# B130B.net
KiCad netlist of a schematic drawn in EAGLE
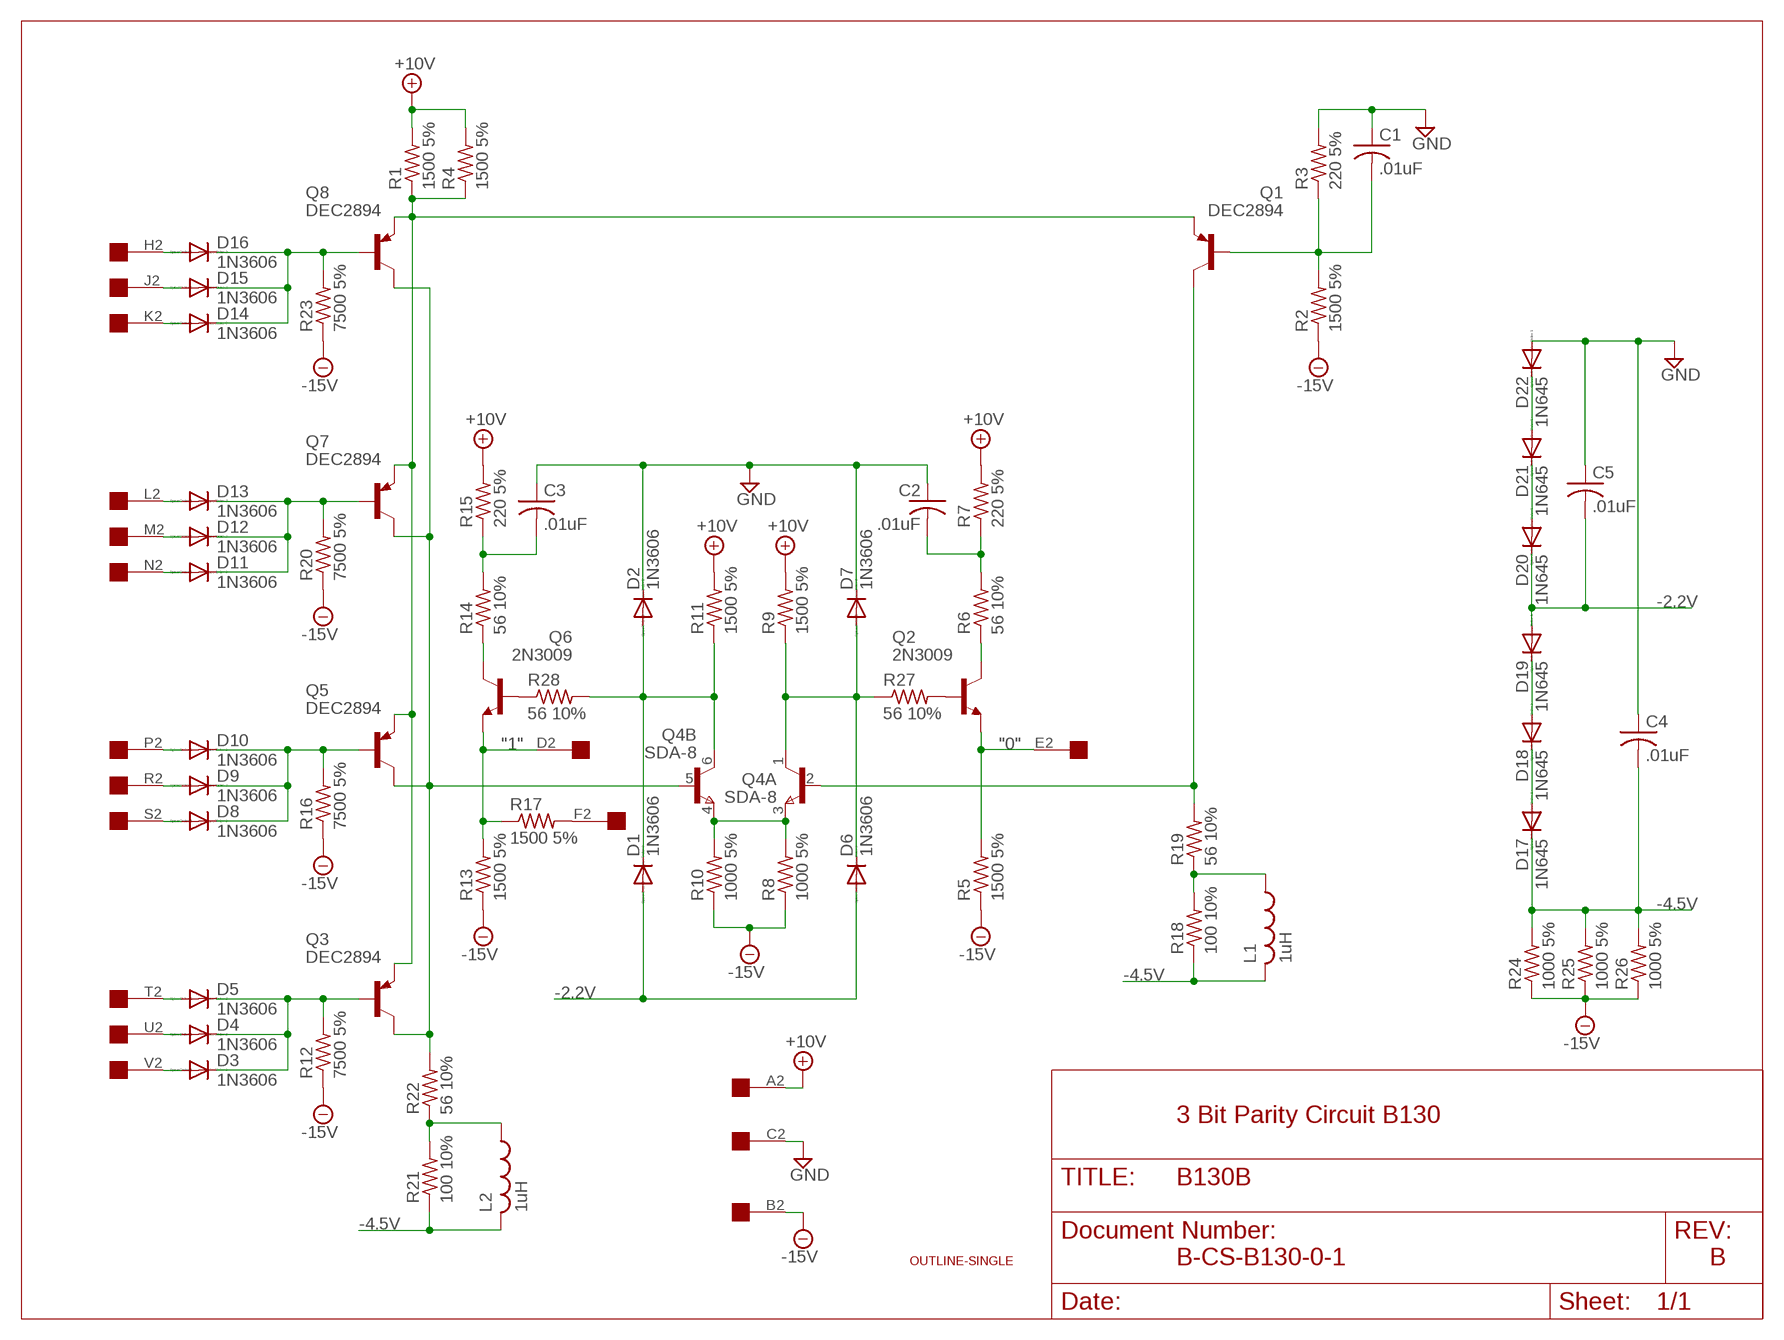
[diagram p0: schematic, sheet 1]

(export (version "E")
  (design (tool "Eeschema 10.0.6"))
  (components
    (comp (ref "C1")
      (value ".01uF")
      (footprint "eagle-import:C050-025X075")
      (libsource (lib "eagle-import") (part "C-US050-025X075"))
    )
    (comp (ref "C2")
      (value ".01uF")
      (footprint "eagle-import:C050-025X075")
      (libsource (lib "eagle-import") (part "C-US050-025X075"))
    )
    (comp (ref "C3")
      (value ".01uF")
      (footprint "eagle-import:C050-025X075")
      (libsource (lib "eagle-import") (part "C-US050-025X075"))
    )
    (comp (ref "C4")
      (value ".01uF")
      (footprint "eagle-import:C050-025X075")
      (libsource (lib "eagle-import") (part "C-US050-025X075"))
    )
    (comp (ref "C5")
      (value ".01uF")
      (footprint "eagle-import:C050-025X075")
      (libsource (lib "eagle-import") (part "C-US050-025X075"))
    )
    (comp (ref "D1")
      (value "1N3606")
      (footprint "eagle-import:DO35-10")
      (libsource (lib "eagle-import") (part "1N4148DO35-10"))
    )
    (comp (ref "D2")
      (value "1N3606")
      (footprint "eagle-import:DO35-10")
      (libsource (lib "eagle-import") (part "1N4148DO35-10"))
    )
    (comp (ref "D3")
      (value "1N3606")
      (footprint "eagle-import:DO35-10")
      (libsource (lib "eagle-import") (part "1N4148DO35-10"))
    )
    (comp (ref "D4")
      (value "1N3606")
      (footprint "eagle-import:DO35-10")
      (libsource (lib "eagle-import") (part "1N4148DO35-10"))
    )
    (comp (ref "D5")
      (value "1N3606")
      (footprint "eagle-import:DO35-10")
      (libsource (lib "eagle-import") (part "1N4148DO35-10"))
    )
    (comp (ref "D6")
      (value "1N3606")
      (footprint "eagle-import:DO35-10")
      (libsource (lib "eagle-import") (part "1N4148DO35-10"))
    )
    (comp (ref "D7")
      (value "1N3606")
      (footprint "eagle-import:DO35-10")
      (libsource (lib "eagle-import") (part "1N4148DO35-10"))
    )
    (comp (ref "D8")
      (value "1N3606")
      (footprint "eagle-import:DO35-10")
      (libsource (lib "eagle-import") (part "1N4148DO35-10"))
    )
    (comp (ref "D9")
      (value "1N3606")
      (footprint "eagle-import:DO35-10")
      (libsource (lib "eagle-import") (part "1N4148DO35-10"))
    )
    (comp (ref "D10")
      (value "1N3606")
      (footprint "eagle-import:DO35-10")
      (libsource (lib "eagle-import") (part "1N4148DO35-10"))
    )
    (comp (ref "D11")
      (value "1N3606")
      (footprint "eagle-import:DO35-10")
      (libsource (lib "eagle-import") (part "1N4148DO35-10"))
    )
    (comp (ref "D12")
      (value "1N3606")
      (footprint "eagle-import:DO35-10")
      (libsource (lib "eagle-import") (part "1N4148DO35-10"))
    )
    (comp (ref "D13")
      (value "1N3606")
      (footprint "eagle-import:DO35-10")
      (libsource (lib "eagle-import") (part "1N4148DO35-10"))
    )
    (comp (ref "D14")
      (value "1N3606")
      (footprint "eagle-import:DO35-10")
      (libsource (lib "eagle-import") (part "1N4148DO35-10"))
    )
    (comp (ref "D15")
      (value "1N3606")
      (footprint "eagle-import:DO35-10")
      (libsource (lib "eagle-import") (part "1N4148DO35-10"))
    )
    (comp (ref "D16")
      (value "1N3606")
      (footprint "eagle-import:DO35-10")
      (libsource (lib "eagle-import") (part "1N4148DO35-10"))
    )
    (comp (ref "D17")
      (value "1N645")
      (footprint "eagle-import:DO35-10")
      (libsource (lib "eagle-import") (part "1N4148DO35-10"))
    )
    (comp (ref "D18")
      (value "1N645")
      (footprint "eagle-import:DO35-10")
      (libsource (lib "eagle-import") (part "1N4148DO35-10"))
    )
    (comp (ref "D19")
      (value "1N645")
      (footprint "eagle-import:DO35-10")
      (libsource (lib "eagle-import") (part "1N4148DO35-10"))
    )
    (comp (ref "D20")
      (value "1N645")
      (footprint "eagle-import:DO35-10")
      (libsource (lib "eagle-import") (part "1N4148DO35-10"))
    )
    (comp (ref "D21")
      (value "1N645")
      (footprint "eagle-import:DO35-10")
      (libsource (lib "eagle-import") (part "1N4148DO35-10"))
    )
    (comp (ref "D22")
      (value "1N645")
      (footprint "eagle-import:DO35-10")
      (libsource (lib "eagle-import") (part "1N4148DO35-10"))
    )
    (comp (ref "L1")
      (value "1uH")
      (footprint "eagle-import:0207_10")
      (libsource (lib "eagle-import") (part "L-US0207/10"))
    )
    (comp (ref "L2")
      (value "1uH")
      (footprint "eagle-import:0207_10")
      (libsource (lib "eagle-import") (part "L-US0207/10"))
    )
    (comp (ref "Q1")
      (value "DEC2894")
      (footprint "eagle-import:TO39")
      (libsource (lib "eagle-import") (part "2N2904"))
    )
    (comp (ref "Q2")
      (value "2N3009")
      (footprint "eagle-import:TO5")
      (libsource (lib "eagle-import") (part "2N2102"))
    )
    (comp (ref "Q3")
      (value "DEC2894")
      (footprint "eagle-import:TO39")
      (libsource (lib "eagle-import") (part "2N2904"))
    )
    (comp (ref "Q4")
      (value "SDA-8")
      (footprint "eagle-import:TO78")
      (libsource (lib "eagle-import") (part "MAT-02H"))
    )
    (comp (ref "Q5")
      (value "DEC2894")
      (footprint "eagle-import:TO39")
      (libsource (lib "eagle-import") (part "2N2904"))
    )
    (comp (ref "Q6")
      (value "2N3009")
      (footprint "eagle-import:TO5")
      (libsource (lib "eagle-import") (part "2N2102"))
    )
    (comp (ref "Q7")
      (value "DEC2894")
      (footprint "eagle-import:TO39")
      (libsource (lib "eagle-import") (part "2N2904"))
    )
    (comp (ref "Q8")
      (value "DEC2894")
      (footprint "eagle-import:TO39")
      (libsource (lib "eagle-import") (part "2N2904"))
    )
    (comp (ref "R1")
      (value "1500 5%")
      (footprint "eagle-import:0207_10")
      (libsource (lib "eagle-import") (part "R-US_0207/10"))
    )
    (comp (ref "R2")
      (value "1500 5%")
      (footprint "eagle-import:0207_10")
      (libsource (lib "eagle-import") (part "R-US_0207/10"))
    )
    (comp (ref "R3")
      (value "220 5%")
      (footprint "eagle-import:0207_10")
      (libsource (lib "eagle-import") (part "R-US_0207/10"))
    )
    (comp (ref "R4")
      (value "1500 5%")
      (footprint "eagle-import:0207_10")
      (libsource (lib "eagle-import") (part "R-US_0207/10"))
    )
    (comp (ref "R5")
      (value "1500 5%")
      (footprint "eagle-import:0207_10")
      (libsource (lib "eagle-import") (part "R-US_0207/10"))
    )
    (comp (ref "R6")
      (value "56 10%")
      (footprint "eagle-import:0207_10")
      (libsource (lib "eagle-import") (part "R-US_0207/10"))
    )
    (comp (ref "R7")
      (value "220 5%")
      (footprint "eagle-import:0207_10")
      (libsource (lib "eagle-import") (part "R-US_0207/10"))
    )
    (comp (ref "R8")
      (value "1000 5%")
      (footprint "eagle-import:0207_10")
      (libsource (lib "eagle-import") (part "R-US_0207/10"))
    )
    (comp (ref "R9")
      (value "1500 5%")
      (footprint "eagle-import:0207_10")
      (libsource (lib "eagle-import") (part "R-US_0207/10"))
    )
    (comp (ref "R10")
      (value "1000 5%")
      (footprint "eagle-import:0207_10")
      (libsource (lib "eagle-import") (part "R-US_0207/10"))
    )
    (comp (ref "R11")
      (value "1500 5%")
      (footprint "eagle-import:0207_10")
      (libsource (lib "eagle-import") (part "R-US_0207/10"))
    )
    (comp (ref "R12")
      (value "7500 5%")
      (footprint "eagle-import:0207_10")
      (libsource (lib "eagle-import") (part "R-US_0207/10"))
    )
    (comp (ref "R13")
      (value "1500 5%")
      (footprint "eagle-import:0207_10")
      (libsource (lib "eagle-import") (part "R-US_0207/10"))
    )
    (comp (ref "R14")
      (value "56 10%")
      (footprint "eagle-import:0207_10")
      (libsource (lib "eagle-import") (part "R-US_0207/10"))
    )
    (comp (ref "R15")
      (value "220 5%")
      (footprint "eagle-import:0207_10")
      (libsource (lib "eagle-import") (part "R-US_0207/10"))
    )
    (comp (ref "R16")
      (value "7500 5%")
      (footprint "eagle-import:0207_10")
      (libsource (lib "eagle-import") (part "R-US_0207/10"))
    )
    (comp (ref "R17")
      (value "1500 5%")
      (footprint "eagle-import:0207_10")
      (libsource (lib "eagle-import") (part "R-US_0207/10"))
    )
    (comp (ref "R18")
      (value "100 10%")
      (footprint "eagle-import:0207_10")
      (libsource (lib "eagle-import") (part "R-US_0207/10"))
    )
    (comp (ref "R19")
      (value "56 10%")
      (footprint "eagle-import:0207_10")
      (libsource (lib "eagle-import") (part "R-US_0207/10"))
    )
    (comp (ref "R20")
      (value "7500 5%")
      (footprint "eagle-import:0207_10")
      (libsource (lib "eagle-import") (part "R-US_0207/10"))
    )
    (comp (ref "R21")
      (value "100 10%")
      (footprint "eagle-import:0207_10")
      (libsource (lib "eagle-import") (part "R-US_0207/10"))
    )
    (comp (ref "R22")
      (value "56 10%")
      (footprint "eagle-import:0207_10")
      (libsource (lib "eagle-import") (part "R-US_0207/10"))
    )
    (comp (ref "R23")
      (value "7500 5%")
      (footprint "eagle-import:0207_10")
      (libsource (lib "eagle-import") (part "R-US_0207/10"))
    )
    (comp (ref "R24")
      (value "1000 5%")
      (footprint "eagle-import:0207_10")
      (libsource (lib "eagle-import") (part "R-US_0207/10"))
    )
    (comp (ref "R25")
      (value "1000 5%")
      (footprint "eagle-import:0207_10")
      (libsource (lib "eagle-import") (part "R-US_0207/10"))
    )
    (comp (ref "R26")
      (value "1000 5%")
      (footprint "eagle-import:0207_10")
      (libsource (lib "eagle-import") (part "R-US_0207/10"))
    )
    (comp (ref "R27")
      (value "56 10%")
      (footprint "eagle-import:0207_10")
      (libsource (lib "eagle-import") (part "R-US_0207/10"))
    )
    (comp (ref "R28")
      (value "56 10%")
      (footprint "eagle-import:0207_10")
      (libsource (lib "eagle-import") (part "R-US_0207/10"))
    )
    (comp (ref "U$1")
      (value "OUTLINE-SINGLE")
      (footprint "eagle-import:SINGLE")
      (libsource (lib "eagle-import") (part "OUTLINE-SINGLE"))
    )
    (comp (ref "U$2")
      (value "EDGE-1")
      (footprint "eagle-import:EDGE-CON1")
      (libsource (lib "eagle-import") (part "EDGE-1"))
    )
  )
  (nets
    (net (code "1") (name "+10V") (class "Default")
      (node (ref "R1") (pin "2") (pinfunction "2_2") (pintype "passive"))
      (node (ref "R11") (pin "2") (pinfunction "2_2") (pintype "passive"))
      (node (ref "R15") (pin "2") (pinfunction "2_2") (pintype "passive"))
      (node (ref "R4") (pin "2") (pinfunction "2_2") (pintype "passive"))
      (node (ref "R7") (pin "2") (pinfunction "2_2") (pintype "passive"))
      (node (ref "R9") (pin "2") (pinfunction "2_2") (pintype "passive"))
      (node (ref "U$2") (pin "A2") (pinfunction "1_A2") (pintype "bidirectional"))
    )
    (net (code "2") (name "-15V") (class "Default")
      (node (ref "R10") (pin "1") (pinfunction "1_1") (pintype "passive"))
      (node (ref "R12") (pin "1") (pinfunction "1_1") (pintype "passive"))
      (node (ref "R13") (pin "1") (pinfunction "1_1") (pintype "passive"))
      (node (ref "R16") (pin "1") (pinfunction "1_1") (pintype "passive"))
      (node (ref "R2") (pin "1") (pinfunction "1_1") (pintype "passive"))
      (node (ref "R20") (pin "1") (pinfunction "1_1") (pintype "passive"))
      (node (ref "R23") (pin "1") (pinfunction "1_1") (pintype "passive"))
      (node (ref "R24") (pin "1") (pinfunction "1_1") (pintype "passive"))
      (node (ref "R25") (pin "1") (pinfunction "1_1") (pintype "passive"))
      (node (ref "R26") (pin "1") (pinfunction "1_1") (pintype "passive"))
      (node (ref "R5") (pin "1") (pinfunction "1_1") (pintype "passive"))
      (node (ref "R8") (pin "1") (pinfunction "1_1") (pintype "passive"))
      (node (ref "U$2") (pin "B2") (pinfunction "1_B2") (pintype "bidirectional"))
    )
    (net (code "3") (name "/\"0\"") (class "Default")
      (node (ref "Q2") (pin "1") (pinfunction "E_1") (pintype "passive"))
      (node (ref "R5") (pin "2") (pinfunction "2_2") (pintype "passive"))
      (node (ref "U$2") (pin "E2") (pinfunction "1_E2") (pintype "bidirectional"))
    )
    (net (code "4") (name "/\"1\"") (class "Default")
      (node (ref "Q6") (pin "1") (pinfunction "E_1") (pintype "passive"))
      (node (ref "R13") (pin "2") (pinfunction "2_2") (pintype "passive"))
      (node (ref "R17") (pin "1") (pinfunction "1_1") (pintype "passive"))
      (node (ref "U$2") (pin "D2") (pinfunction "1_D2") (pintype "bidirectional"))
    )
    (net (code "5") (name "/-2.2V") (class "Default")
      (node (ref "C5") (pin "2") (pinfunction "2_2") (pintype "passive"))
      (node (ref "D1") (pin "A") (pinfunction "A_A") (pintype "passive"))
      (node (ref "D19") (pin "A") (pinfunction "A_A") (pintype "passive"))
      (node (ref "D20") (pin "C") (pinfunction "C_C") (pintype "passive"))
      (node (ref "D6") (pin "A") (pinfunction "A_A") (pintype "passive"))
    )
    (net (code "6") (name "/-4.5V") (class "Default")
      (node (ref "C4") (pin "2") (pinfunction "2_2") (pintype "passive"))
      (node (ref "D17") (pin "C") (pinfunction "C_C") (pintype "passive"))
      (node (ref "L1") (pin "2") (pinfunction "2_2") (pintype "passive"))
      (node (ref "L2") (pin "2") (pinfunction "2_2") (pintype "passive"))
      (node (ref "R18") (pin "1") (pinfunction "1_1") (pintype "passive"))
      (node (ref "R21") (pin "1") (pinfunction "1_1") (pintype "passive"))
      (node (ref "R24") (pin "2") (pinfunction "2_2") (pintype "passive"))
      (node (ref "R25") (pin "2") (pinfunction "2_2") (pintype "passive"))
      (node (ref "R26") (pin "2") (pinfunction "2_2") (pintype "passive"))
    )
    (net (code "7") (name "GND") (class "Default")
      (node (ref "C1") (pin "1") (pinfunction "1_1") (pintype "passive"))
      (node (ref "C2") (pin "1") (pinfunction "1_1") (pintype "passive"))
      (node (ref "C3") (pin "1") (pinfunction "1_1") (pintype "passive"))
      (node (ref "C4") (pin "1") (pinfunction "1_1") (pintype "passive"))
      (node (ref "C5") (pin "1") (pinfunction "1_1") (pintype "passive"))
      (node (ref "D2") (pin "C") (pinfunction "C_C") (pintype "passive"))
      (node (ref "D22") (pin "A") (pinfunction "A_A") (pintype "passive"))
      (node (ref "D7") (pin "C") (pinfunction "C_C") (pintype "passive"))
      (node (ref "R3") (pin "2") (pinfunction "2_2") (pintype "passive"))
      (node (ref "U$2") (pin "C2") (pinfunction "1_C2") (pintype "bidirectional"))
    )
    (net (code "8") (name "Net-(C2-Pad2)") (class "Default")
      (node (ref "C2") (pin "2") (pinfunction "2_2") (pintype "passive"))
      (node (ref "R6") (pin "2") (pinfunction "2_2") (pintype "passive"))
      (node (ref "R7") (pin "1") (pinfunction "1_1") (pintype "passive"))
    )
    (net (code "9") (name "Net-(C3-Pad2)") (class "Default")
      (node (ref "C3") (pin "2") (pinfunction "2_2") (pintype "passive"))
      (node (ref "R14") (pin "2") (pinfunction "2_2") (pintype "passive"))
      (node (ref "R15") (pin "1") (pinfunction "1_1") (pintype "passive"))
    )
    (net (code "10") (name "Net-(D17-PadA)") (class "Default")
      (node (ref "D17") (pin "A") (pinfunction "A_A") (pintype "passive"))
      (node (ref "D18") (pin "C") (pinfunction "C_C") (pintype "passive"))
    )
    (net (code "11") (name "Net-(D18-PadA)") (class "Default")
      (node (ref "D18") (pin "A") (pinfunction "A_A") (pintype "passive"))
      (node (ref "D19") (pin "C") (pinfunction "C_C") (pintype "passive"))
    )
    (net (code "12") (name "Net-(D20-PadA)") (class "Default")
      (node (ref "D20") (pin "A") (pinfunction "A_A") (pintype "passive"))
      (node (ref "D21") (pin "C") (pinfunction "C_C") (pintype "passive"))
    )
    (net (code "13") (name "Net-(D21-PadA)") (class "Default")
      (node (ref "D21") (pin "A") (pinfunction "A_A") (pintype "passive"))
      (node (ref "D22") (pin "C") (pinfunction "C_C") (pintype "passive"))
    )
    (net (code "14") (name "Net-(L1-Pad1)") (class "Default")
      (node (ref "L1") (pin "1") (pinfunction "1_1") (pintype "passive"))
      (node (ref "R18") (pin "2") (pinfunction "2_2") (pintype "passive"))
      (node (ref "R19") (pin "1") (pinfunction "1_1") (pintype "passive"))
    )
    (net (code "15") (name "Net-(L2-Pad1)") (class "Default")
      (node (ref "L2") (pin "1") (pinfunction "1_1") (pintype "passive"))
      (node (ref "R21") (pin "2") (pinfunction "2_2") (pintype "passive"))
      (node (ref "R22") (pin "1") (pinfunction "1_1") (pintype "passive"))
    )
    (net (code "16") (name "Net-(Q1-B)") (class "Default")
      (node (ref "C1") (pin "2") (pinfunction "2_2") (pintype "passive"))
      (node (ref "Q1") (pin "2") (pinfunction "B_2") (pintype "passive"))
      (node (ref "R2") (pin "2") (pinfunction "2_2") (pintype "passive"))
      (node (ref "R3") (pin "1") (pinfunction "1_1") (pintype "passive"))
    )
    (net (code "17") (name "Net-(Q1-C)") (class "Default")
      (node (ref "Q1") (pin "3") (pinfunction "C_3") (pintype "passive"))
      (node (ref "Q4") (pin "2") (pinfunction "B_2") (pintype "passive"))
      (node (ref "R19") (pin "2") (pinfunction "2_2") (pintype "passive"))
    )
    (net (code "18") (name "Net-(Q1-E)") (class "Default")
      (node (ref "Q1") (pin "1") (pinfunction "E_1") (pintype "passive"))
      (node (ref "Q3") (pin "1") (pinfunction "E_1") (pintype "passive"))
      (node (ref "Q5") (pin "1") (pinfunction "E_1") (pintype "passive"))
      (node (ref "Q7") (pin "1") (pinfunction "E_1") (pintype "passive"))
      (node (ref "Q8") (pin "1") (pinfunction "E_1") (pintype "passive"))
      (node (ref "R1") (pin "1") (pinfunction "1_1") (pintype "passive"))
      (node (ref "R4") (pin "1") (pinfunction "1_1") (pintype "passive"))
    )
    (net (code "19") (name "Net-(Q2-B)") (class "Default")
      (node (ref "Q2") (pin "2") (pinfunction "B_2") (pintype "passive"))
      (node (ref "R27") (pin "2") (pinfunction "2_2") (pintype "passive"))
    )
    (net (code "20") (name "Net-(Q2-C)") (class "Default")
      (node (ref "Q2") (pin "3") (pinfunction "C_3") (pintype "passive"))
      (node (ref "R6") (pin "1") (pinfunction "1_1") (pintype "passive"))
    )
    (net (code "21") (name "Net-(Q3-B)") (class "Default")
      (node (ref "D3") (pin "C") (pinfunction "C_C") (pintype "passive"))
      (node (ref "D4") (pin "C") (pinfunction "C_C") (pintype "passive"))
      (node (ref "D5") (pin "C") (pinfunction "C_C") (pintype "passive"))
      (node (ref "Q3") (pin "2") (pinfunction "B_2") (pintype "passive"))
      (node (ref "R12") (pin "2") (pinfunction "2_2") (pintype "passive"))
    )
    (net (code "22") (name "Net-(Q3-C)") (class "Default")
      (node (ref "Q3") (pin "3") (pinfunction "C_3") (pintype "passive"))
      (node (ref "Q4") (pin "5") (pinfunction "B_5") (pintype "passive"))
      (node (ref "Q5") (pin "3") (pinfunction "C_3") (pintype "passive"))
      (node (ref "Q7") (pin "3") (pinfunction "C_3") (pintype "passive"))
      (node (ref "Q8") (pin "3") (pinfunction "C_3") (pintype "passive"))
      (node (ref "R22") (pin "2") (pinfunction "2_2") (pintype "passive"))
    )
    (net (code "23") (name "Net-(Q4A-C)") (class "Default")
      (node (ref "D6") (pin "C") (pinfunction "C_C") (pintype "passive"))
      (node (ref "D7") (pin "A") (pinfunction "A_A") (pintype "passive"))
      (node (ref "Q4") (pin "1") (pinfunction "C_1") (pintype "passive"))
      (node (ref "R27") (pin "1") (pinfunction "1_1") (pintype "passive"))
      (node (ref "R9") (pin "1") (pinfunction "1_1") (pintype "passive"))
    )
    (net (code "24") (name "Net-(Q4A-E)") (class "Default")
      (node (ref "Q4") (pin "3") (pinfunction "E_3") (pintype "passive"))
      (node (ref "Q4") (pin "4") (pinfunction "E_4") (pintype "passive"))
      (node (ref "R10") (pin "2") (pinfunction "2_2") (pintype "passive"))
      (node (ref "R8") (pin "2") (pinfunction "2_2") (pintype "passive"))
    )
    (net (code "25") (name "Net-(Q4B-C)") (class "Default")
      (node (ref "D1") (pin "C") (pinfunction "C_C") (pintype "passive"))
      (node (ref "D2") (pin "A") (pinfunction "A_A") (pintype "passive"))
      (node (ref "Q4") (pin "6") (pinfunction "C_6") (pintype "passive"))
      (node (ref "R11") (pin "1") (pinfunction "1_1") (pintype "passive"))
      (node (ref "R28") (pin "2") (pinfunction "2_2") (pintype "passive"))
    )
    (net (code "26") (name "Net-(Q5-B)") (class "Default")
      (node (ref "D10") (pin "C") (pinfunction "C_C") (pintype "passive"))
      (node (ref "D8") (pin "C") (pinfunction "C_C") (pintype "passive"))
      (node (ref "D9") (pin "C") (pinfunction "C_C") (pintype "passive"))
      (node (ref "Q5") (pin "2") (pinfunction "B_2") (pintype "passive"))
      (node (ref "R16") (pin "2") (pinfunction "2_2") (pintype "passive"))
    )
    (net (code "27") (name "Net-(Q6-B)") (class "Default")
      (node (ref "Q6") (pin "2") (pinfunction "B_2") (pintype "passive"))
      (node (ref "R28") (pin "1") (pinfunction "1_1") (pintype "passive"))
    )
    (net (code "28") (name "Net-(Q6-C)") (class "Default")
      (node (ref "Q6") (pin "3") (pinfunction "C_3") (pintype "passive"))
      (node (ref "R14") (pin "1") (pinfunction "1_1") (pintype "passive"))
    )
    (net (code "29") (name "Net-(Q7-B)") (class "Default")
      (node (ref "D11") (pin "C") (pinfunction "C_C") (pintype "passive"))
      (node (ref "D12") (pin "C") (pinfunction "C_C") (pintype "passive"))
      (node (ref "D13") (pin "C") (pinfunction "C_C") (pintype "passive"))
      (node (ref "Q7") (pin "2") (pinfunction "B_2") (pintype "passive"))
      (node (ref "R20") (pin "2") (pinfunction "2_2") (pintype "passive"))
    )
    (net (code "30") (name "Net-(Q8-B)") (class "Default")
      (node (ref "D14") (pin "C") (pinfunction "C_C") (pintype "passive"))
      (node (ref "D15") (pin "C") (pinfunction "C_C") (pintype "passive"))
      (node (ref "D16") (pin "C") (pinfunction "C_C") (pintype "passive"))
      (node (ref "Q8") (pin "2") (pinfunction "B_2") (pintype "passive"))
      (node (ref "R23") (pin "2") (pinfunction "2_2") (pintype "passive"))
    )
    (net (code "31") (name "Net-(U$2F-1)") (class "Default")
      (node (ref "R17") (pin "2") (pinfunction "2_2") (pintype "passive"))
      (node (ref "U$2") (pin "F2") (pinfunction "1_F2") (pintype "bidirectional"))
    )
    (net (code "32") (name "Net-(U$2G-1)") (class "Default")
      (node (ref "D16") (pin "A") (pinfunction "A_A") (pintype "passive"))
      (node (ref "U$2") (pin "H2") (pinfunction "1_H2") (pintype "bidirectional"))
    )
    (net (code "33") (name "Net-(U$2H-1)") (class "Default")
      (node (ref "D15") (pin "A") (pinfunction "A_A") (pintype "passive"))
      (node (ref "U$2") (pin "J2") (pinfunction "1_J2") (pintype "bidirectional"))
    )
    (net (code "34") (name "Net-(U$2I-1)") (class "Default")
      (node (ref "D14") (pin "A") (pinfunction "A_A") (pintype "passive"))
      (node (ref "U$2") (pin "K2") (pinfunction "1_K2") (pintype "bidirectional"))
    )
    (net (code "35") (name "Net-(U$2J-1)") (class "Default")
      (node (ref "D13") (pin "A") (pinfunction "A_A") (pintype "passive"))
      (node (ref "U$2") (pin "L2") (pinfunction "1_L2") (pintype "bidirectional"))
    )
    (net (code "36") (name "Net-(U$2K-1)") (class "Default")
      (node (ref "D12") (pin "A") (pinfunction "A_A") (pintype "passive"))
      (node (ref "U$2") (pin "M2") (pinfunction "1_M2") (pintype "bidirectional"))
    )
    (net (code "37") (name "Net-(U$2L-1)") (class "Default")
      (node (ref "D11") (pin "A") (pinfunction "A_A") (pintype "passive"))
      (node (ref "U$2") (pin "N2") (pinfunction "1_N2") (pintype "bidirectional"))
    )
    (net (code "38") (name "Net-(U$2M-1)") (class "Default")
      (node (ref "D10") (pin "A") (pinfunction "A_A") (pintype "passive"))
      (node (ref "U$2") (pin "P2") (pinfunction "1_P2") (pintype "bidirectional"))
    )
    (net (code "39") (name "Net-(U$2N-1)") (class "Default")
      (node (ref "D9") (pin "A") (pinfunction "A_A") (pintype "passive"))
      (node (ref "U$2") (pin "R2") (pinfunction "1_R2") (pintype "bidirectional"))
    )
    (net (code "40") (name "Net-(U$2O-1)") (class "Default")
      (node (ref "D8") (pin "A") (pinfunction "A_A") (pintype "passive"))
      (node (ref "U$2") (pin "S2") (pinfunction "1_S2") (pintype "bidirectional"))
    )
    (net (code "41") (name "Net-(U$2P-1)") (class "Default")
      (node (ref "D5") (pin "A") (pinfunction "A_A") (pintype "passive"))
      (node (ref "U$2") (pin "T2") (pinfunction "1_T2") (pintype "bidirectional"))
    )
    (net (code "42") (name "Net-(U$2Q-1)") (class "Default")
      (node (ref "D4") (pin "A") (pinfunction "A_A") (pintype "passive"))
      (node (ref "U$2") (pin "U2") (pinfunction "1_U2") (pintype "bidirectional"))
    )
    (net (code "43") (name "Net-(U$2R-1)") (class "Default")
      (node (ref "D3") (pin "A") (pinfunction "A_A") (pintype "passive"))
      (node (ref "U$2") (pin "V2") (pinfunction "1_V2") (pintype "bidirectional"))
    )
  )
)
